# VAR-PBB_v02.net
KiCad netlist of a schematic drawn in EAGLE
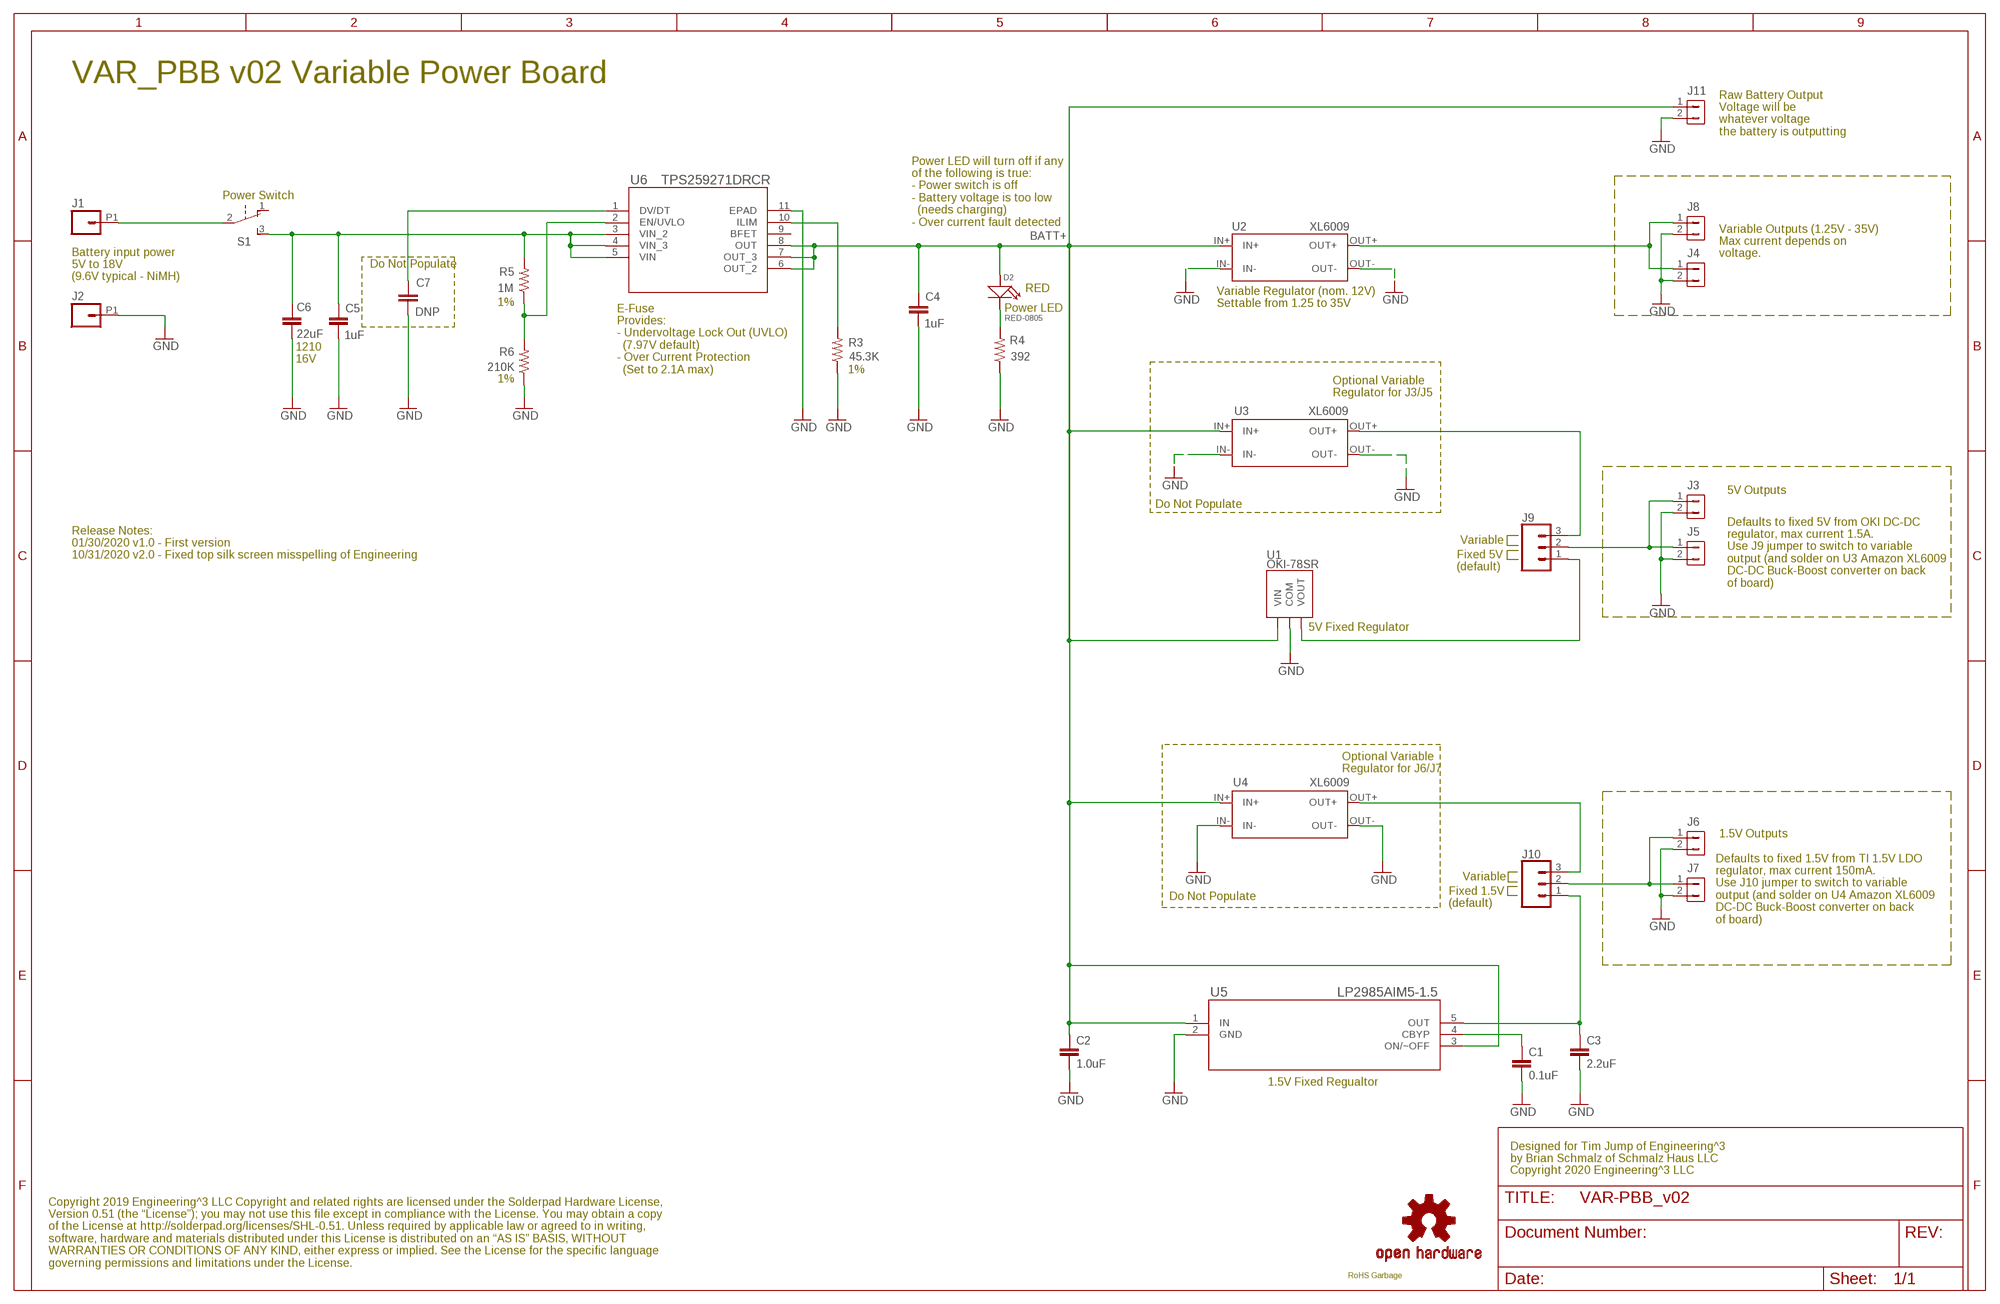
[diagram p0: schematic, sheet 1]

(export (version "E")
  (design (tool "Eeschema 10.0.6"))
  (components
    (comp (ref "C1")
      (value "0.1uF")
      (footprint "eagle-import:0603")
      (libsource (lib "eagle-import") (part "0.1UF-0603-25V-5%"))
    )
    (comp (ref "C2")
      (value "1.0uF")
      (footprint "eagle-import:0603")
      (libsource (lib "eagle-import") (part "1.0UF-0603-16V-10%"))
    )
    (comp (ref "C3")
      (value "2.2uF")
      (footprint "eagle-import:0603")
      (libsource (lib "eagle-import") (part "2.2UF-0603-10V-20%"))
    )
    (comp (ref "C4")
      (value "1uF")
      (footprint "eagle-import:0603")
      (libsource (lib "eagle-import") (part "0.1UF-0603-25V-5%"))
    )
    (comp (ref "C5")
      (value "1uF")
      (footprint "eagle-import:0603")
      (libsource (lib "eagle-import") (part "0.1UF-0603-25V-5%"))
    )
    (comp (ref "C6")
      (value "22uF")
      (footprint "eagle-import:1210")
      (libsource (lib "eagle-import") (part "22UF-1210-16V-20%"))
    )
    (comp (ref "C7")
      (value "DNP")
      (footprint "eagle-import:0603")
      (libsource (lib "eagle-import") (part "0.1UF-0603-25V-5%"))
    )
    (comp (ref "D2")
      (value "RED-0805")
      (footprint "eagle-import:LED-0805")
      (fields (field (name "MPN") "17-215SURC/S530-A2/TR8"))
      (libsource (lib "eagle-import") (part "SMD-LED-CLEAR-RED(0805)"))
    )
    (comp (ref "J1")
      (value "ANDERSON_POWER_POLE")
      (footprint "eagle-import:ANDERSON_POWER_POLE")
      (libsource (lib "eagle-import") (part "ANDERSON_POWER_POLE"))
    )
    (comp (ref "J2")
      (value "ANDERSON_POWER_POLE")
      (footprint "eagle-import:ANDERSON_POWER_POLE")
      (libsource (lib "eagle-import") (part "ANDERSON_POWER_POLE"))
    )
    (comp (ref "J3")
      (value "CON1X2_SHROUDED")
      (footprint "eagle-import:HEADER_1X2_SHROUDED")
      (libsource (lib "eagle-import") (part "CON1X2_SHROUDED"))
    )
    (comp (ref "J4")
      (value "CON1X2_SHROUDED")
      (footprint "eagle-import:HEADER_1X2_SHROUDED")
      (libsource (lib "eagle-import") (part "CON1X2_SHROUDED"))
    )
    (comp (ref "J5")
      (value "CON1X2_SHROUDED")
      (footprint "eagle-import:HEADER_1X2_SHROUDED")
      (libsource (lib "eagle-import") (part "CON1X2_SHROUDED"))
    )
    (comp (ref "J6")
      (value "CON1X2_SHROUDED")
      (footprint "eagle-import:HEADER_1X2_SHROUDED")
      (libsource (lib "eagle-import") (part "CON1X2_SHROUDED"))
    )
    (comp (ref "J7")
      (value "CON1X2_SHROUDED")
      (footprint "eagle-import:HEADER_1X2_SHROUDED")
      (libsource (lib "eagle-import") (part "CON1X2_SHROUDED"))
    )
    (comp (ref "J8")
      (value "CON1X2_SHROUDED")
      (footprint "eagle-import:HEADER_1X2_SHROUDED")
      (libsource (lib "eagle-import") (part "CON1X2_SHROUDED"))
    )
    (comp (ref "J9")
      (value "CONN_03")
      (footprint "eagle-import:1X03")
      (libsource (lib "eagle-import") (part "CONN_03"))
    )
    (comp (ref "J10")
      (value "CONN_03")
      (footprint "eagle-import:1X03")
      (libsource (lib "eagle-import") (part "CONN_03"))
    )
    (comp (ref "J11")
      (value "CON1X2_SHROUDED")
      (footprint "eagle-import:HEADER_1X2_SHROUDED")
      (libsource (lib "eagle-import") (part "CON1X2_SHROUDED"))
    )
    (comp (ref "LOGO2")
      (value "OSHW-LOGOM")
      (footprint "eagle-import:OSHW-LOGO-M")
      (libsource (lib "eagle-import") (part "OSHW-LOGOM"))
    )
    (comp (ref "R3")
      (value "45.3K")
      (footprint "eagle-import:0603")
      (libsource (lib "eagle-import") (part "RESISTOR0603"))
    )
    (comp (ref "R4")
      (value "392")
      (footprint "eagle-import:0603")
      (libsource (lib "eagle-import") (part "RESISTOR0603"))
    )
    (comp (ref "R5")
      (value "1M")
      (footprint "eagle-import:0603")
      (libsource (lib "eagle-import") (part "RESISTOR0603"))
    )
    (comp (ref "R6")
      (value "210K")
      (footprint "eagle-import:0603")
      (libsource (lib "eagle-import") (part "RESISTOR0603"))
    )
    (comp (ref "S1")
      (value "SWITCH_SLIDE_ON_ON")
      (footprint "eagle-import:SWITCH_SLIDE_RA")
      (libsource (lib "eagle-import") (part "SWITCH_SLIDE_ON_ON"))
    )
    (comp (ref "U$6")
      (value "ROHS_GARBAGE")
      (footprint "eagle-import:ROHS_GARBAGE_5MM")
      (libsource (lib "eagle-import") (part "ROHS_GARBAGE"))
    )
    (comp (ref "U1")
      (value "OKI-78SR")
      (footprint "eagle-import:OKI-78SR_REGULATOR_HORIZONTAL")
      (libsource (lib "eagle-import") (part "OKI-78SR"))
    )
    (comp (ref "U2")
      (value "XL6009")
      (footprint "eagle-import:XL6009_MODULE")
      (libsource (lib "eagle-import") (part "XL6009"))
    )
    (comp (ref "U3")
      (value "XL6009")
      (footprint "eagle-import:XL6009_MODULE")
      (libsource (lib "eagle-import") (part "XL6009"))
    )
    (comp (ref "U4")
      (value "XL6009")
      (footprint "eagle-import:XL6009_MODULE")
      (libsource (lib "eagle-import") (part "XL6009"))
    )
    (comp (ref "U5")
      (value "LP2985AIM5-1.5")
      (footprint "eagle-import:MF05A")
      (fields (field (name "COPYRIGHT") "Copyright (C) 2018 Accelerated Designs. All rights reserved"))
      (libsource (lib "eagle-import") (part "LP2985AIM5-1.5"))
    )
    (comp (ref "U6")
      (value "TPS259271DRCR")
      (footprint "eagle-import:DRC10_1P65X2P40")
      (fields (field (name "COPYRIGHT") "Copyright (C) 2018 Accelerated Designs. All rights reserved"))
      (libsource (lib "eagle-import") (part "TPS259271DRCR"))
    )
  )
  (nets
    (net (code "1") (name "/BATT+") (class "Default")
      (node (ref "C2") (pin "1") (pinfunction "1_1") (pintype "passive"))
      (node (ref "C4") (pin "2") (pinfunction "2_2") (pintype "passive"))
      (node (ref "D2") (pin "+") (pinfunction "+_+") (pintype "passive"))
      (node (ref "J11") (pin "1") (pinfunction "1_1") (pintype "passive"))
      (node (ref "U1") (pin "P$1") (pinfunction "VIN_P$1") (pintype "bidirectional"))
      (node (ref "U2") (pin "IN+") (pinfunction "IN+_IN+") (pintype "bidirectional"))
      (node (ref "U3") (pin "IN+") (pinfunction "IN+_IN+") (pintype "bidirectional"))
      (node (ref "U4") (pin "IN+") (pinfunction "IN+_IN+") (pintype "bidirectional"))
      (node (ref "U5") (pin "1") (pinfunction "IN_1") (pintype "power_in"))
      (node (ref "U5") (pin "3") (pinfunction "ON/~{OFF}_3") (pintype "input"))
      (node (ref "U6") (pin "6") (pinfunction "OUT_2_6") (pintype "output"))
      (node (ref "U6") (pin "7") (pinfunction "OUT_3_7") (pintype "output"))
      (node (ref "U6") (pin "8") (pinfunction "OUT_8") (pintype "output"))
    )
    (net (code "2") (name "GND") (class "Default")
      (node (ref "C1") (pin "2") (pinfunction "2_2") (pintype "passive"))
      (node (ref "C2") (pin "2") (pinfunction "2_2") (pintype "passive"))
      (node (ref "C3") (pin "2") (pinfunction "2_2") (pintype "passive"))
      (node (ref "C4") (pin "1") (pinfunction "1_1") (pintype "passive"))
      (node (ref "C5") (pin "1") (pinfunction "1_1") (pintype "passive"))
      (node (ref "C6") (pin "2") (pinfunction "2_2") (pintype "passive"))
      (node (ref "C7") (pin "1") (pinfunction "1_1") (pintype "passive"))
      (node (ref "J11") (pin "2") (pinfunction "2_2") (pintype "passive"))
      (node (ref "J2") (pin "P1") (pinfunction "5_P1") (pintype "passive"))
      (node (ref "J3") (pin "2") (pinfunction "2_2") (pintype "passive"))
      (node (ref "J4") (pin "2") (pinfunction "2_2") (pintype "passive"))
      (node (ref "J5") (pin "2") (pinfunction "2_2") (pintype "passive"))
      (node (ref "J6") (pin "2") (pinfunction "2_2") (pintype "passive"))
      (node (ref "J7") (pin "2") (pinfunction "2_2") (pintype "passive"))
      (node (ref "J8") (pin "2") (pinfunction "2_2") (pintype "passive"))
      (node (ref "R3") (pin "1") (pinfunction "1_1") (pintype "passive"))
      (node (ref "R4") (pin "1") (pinfunction "1_1") (pintype "passive"))
      (node (ref "R6") (pin "1") (pinfunction "1_1") (pintype "passive"))
      (node (ref "U1") (pin "P$2") (pinfunction "COM_P$2") (pintype "bidirectional"))
      (node (ref "U2") (pin "IN-") (pinfunction "IN-_IN-") (pintype "bidirectional"))
      (node (ref "U2") (pin "OUT-") (pinfunction "OUT-_OUT-") (pintype "bidirectional"))
      (node (ref "U3") (pin "IN-") (pinfunction "IN-_IN-") (pintype "bidirectional"))
      (node (ref "U3") (pin "OUT-") (pinfunction "OUT-_OUT-") (pintype "bidirectional"))
      (node (ref "U4") (pin "IN-") (pinfunction "IN-_IN-") (pintype "bidirectional"))
      (node (ref "U4") (pin "OUT-") (pinfunction "OUT-_OUT-") (pintype "bidirectional"))
      (node (ref "U5") (pin "2") (pinfunction "GND_2") (pintype "power_in"))
      (node (ref "U6") (pin "11") (pinfunction "EPAD_11") (pintype "passive"))
    )
    (net (code "3") (name "Net-(D2-Pad-)") (class "Default")
      (node (ref "D2") (pin "-") (pinfunction "-_-") (pintype "passive"))
      (node (ref "R4") (pin "2") (pinfunction "2_2") (pintype "passive"))
    )
    (net (code "4") (name "Net-(J1-5)") (class "Default")
      (node (ref "J1") (pin "P1") (pinfunction "5_P1") (pintype "passive"))
      (node (ref "S1") (pin "2") (pinfunction "P_2") (pintype "passive"))
    )
    (net (code "5") (name "Net-(J3-Pad1)") (class "Default")
      (node (ref "J3") (pin "1") (pinfunction "1_1") (pintype "passive"))
      (node (ref "J5") (pin "1") (pinfunction "1_1") (pintype "passive"))
      (node (ref "J9") (pin "2") (pinfunction "2_2") (pintype "passive"))
    )
    (net (code "6") (name "Net-(J4-Pad1)") (class "Default")
      (node (ref "J4") (pin "1") (pinfunction "1_1") (pintype "passive"))
      (node (ref "J8") (pin "1") (pinfunction "1_1") (pintype "passive"))
      (node (ref "U2") (pin "OUT+") (pinfunction "OUT+_OUT+") (pintype "bidirectional"))
    )
    (net (code "7") (name "Net-(J9-Pad3)") (class "Default")
      (node (ref "J9") (pin "3") (pinfunction "3_3") (pintype "passive"))
      (node (ref "U3") (pin "OUT+") (pinfunction "OUT+_OUT+") (pintype "bidirectional"))
    )
    (net (code "8") (name "Net-(J10-Pad2)") (class "Default")
      (node (ref "J10") (pin "2") (pinfunction "2_2") (pintype "passive"))
      (node (ref "J6") (pin "1") (pinfunction "1_1") (pintype "passive"))
      (node (ref "J7") (pin "1") (pinfunction "1_1") (pintype "passive"))
    )
    (net (code "9") (name "Net-(J10-Pad3)") (class "Default")
      (node (ref "J10") (pin "3") (pinfunction "3_3") (pintype "passive"))
      (node (ref "U4") (pin "OUT+") (pinfunction "OUT+_OUT+") (pintype "bidirectional"))
    )
    (net (code "10") (name "Net-(S1-S)") (class "Default")
      (node (ref "C5") (pin "2") (pinfunction "2_2") (pintype "passive"))
      (node (ref "C6") (pin "1") (pinfunction "1_1") (pintype "passive"))
      (node (ref "R5") (pin "2") (pinfunction "2_2") (pintype "passive"))
      (node (ref "S1") (pin "3") (pinfunction "S_3") (pintype "passive"))
      (node (ref "U6") (pin "3") (pinfunction "VIN_2_3") (pintype "passive"))
      (node (ref "U6") (pin "4") (pinfunction "VIN_3_4") (pintype "passive"))
      (node (ref "U6") (pin "5") (pinfunction "VIN_5") (pintype "passive"))
    )
    (net (code "11") (name "Net-(U1-VOUT)") (class "Default")
      (node (ref "J9") (pin "1") (pinfunction "1_1") (pintype "passive"))
      (node (ref "U1") (pin "P$3") (pinfunction "VOUT_P$3") (pintype "bidirectional"))
    )
    (net (code "12") (name "Net-(U5-CBYP)") (class "Default")
      (node (ref "C1") (pin "1") (pinfunction "1_1") (pintype "passive"))
      (node (ref "U5") (pin "4") (pinfunction "CBYP_4") (pintype "passive"))
    )
    (net (code "13") (name "Net-(U5-OUT)") (class "Default")
      (node (ref "C3") (pin "1") (pinfunction "1_1") (pintype "passive"))
      (node (ref "J10") (pin "1") (pinfunction "1_1") (pintype "passive"))
      (node (ref "U5") (pin "5") (pinfunction "OUT_5") (pintype "power_in"))
    )
    (net (code "14") (name "Net-(U6-DV{slash}DT)") (class "Default")
      (node (ref "C7") (pin "2") (pinfunction "2_2") (pintype "passive"))
      (node (ref "U6") (pin "1") (pinfunction "DV/DT_1") (pintype "passive"))
    )
    (net (code "15") (name "Net-(U6-EN{slash}UVLO)") (class "Default")
      (node (ref "R5") (pin "1") (pinfunction "1_1") (pintype "passive"))
      (node (ref "R6") (pin "2") (pinfunction "2_2") (pintype "passive"))
      (node (ref "U6") (pin "2") (pinfunction "EN/UVLO_2") (pintype "passive"))
    )
    (net (code "16") (name "Net-(U6-ILIM)") (class "Default")
      (node (ref "R3") (pin "2") (pinfunction "2_2") (pintype "passive"))
      (node (ref "U6") (pin "10") (pinfunction "ILIM_10") (pintype "passive"))
    )
    (net (code "17") (name "unconnected-(S1-O-Pad1)") (class "Default")
      (node (ref "S1") (pin "1") (pinfunction "O_1") (pintype "passive"))
    )
    (net (code "18") (name "unconnected-(U6-BFET-Pad9)") (class "Default")
      (node (ref "U6") (pin "9") (pinfunction "BFET_9") (pintype "passive"))
    )
  )
)
